# FAN_CONTROLER_LDO.net
KiCad netlist of a schematic drawn in EasyEDA
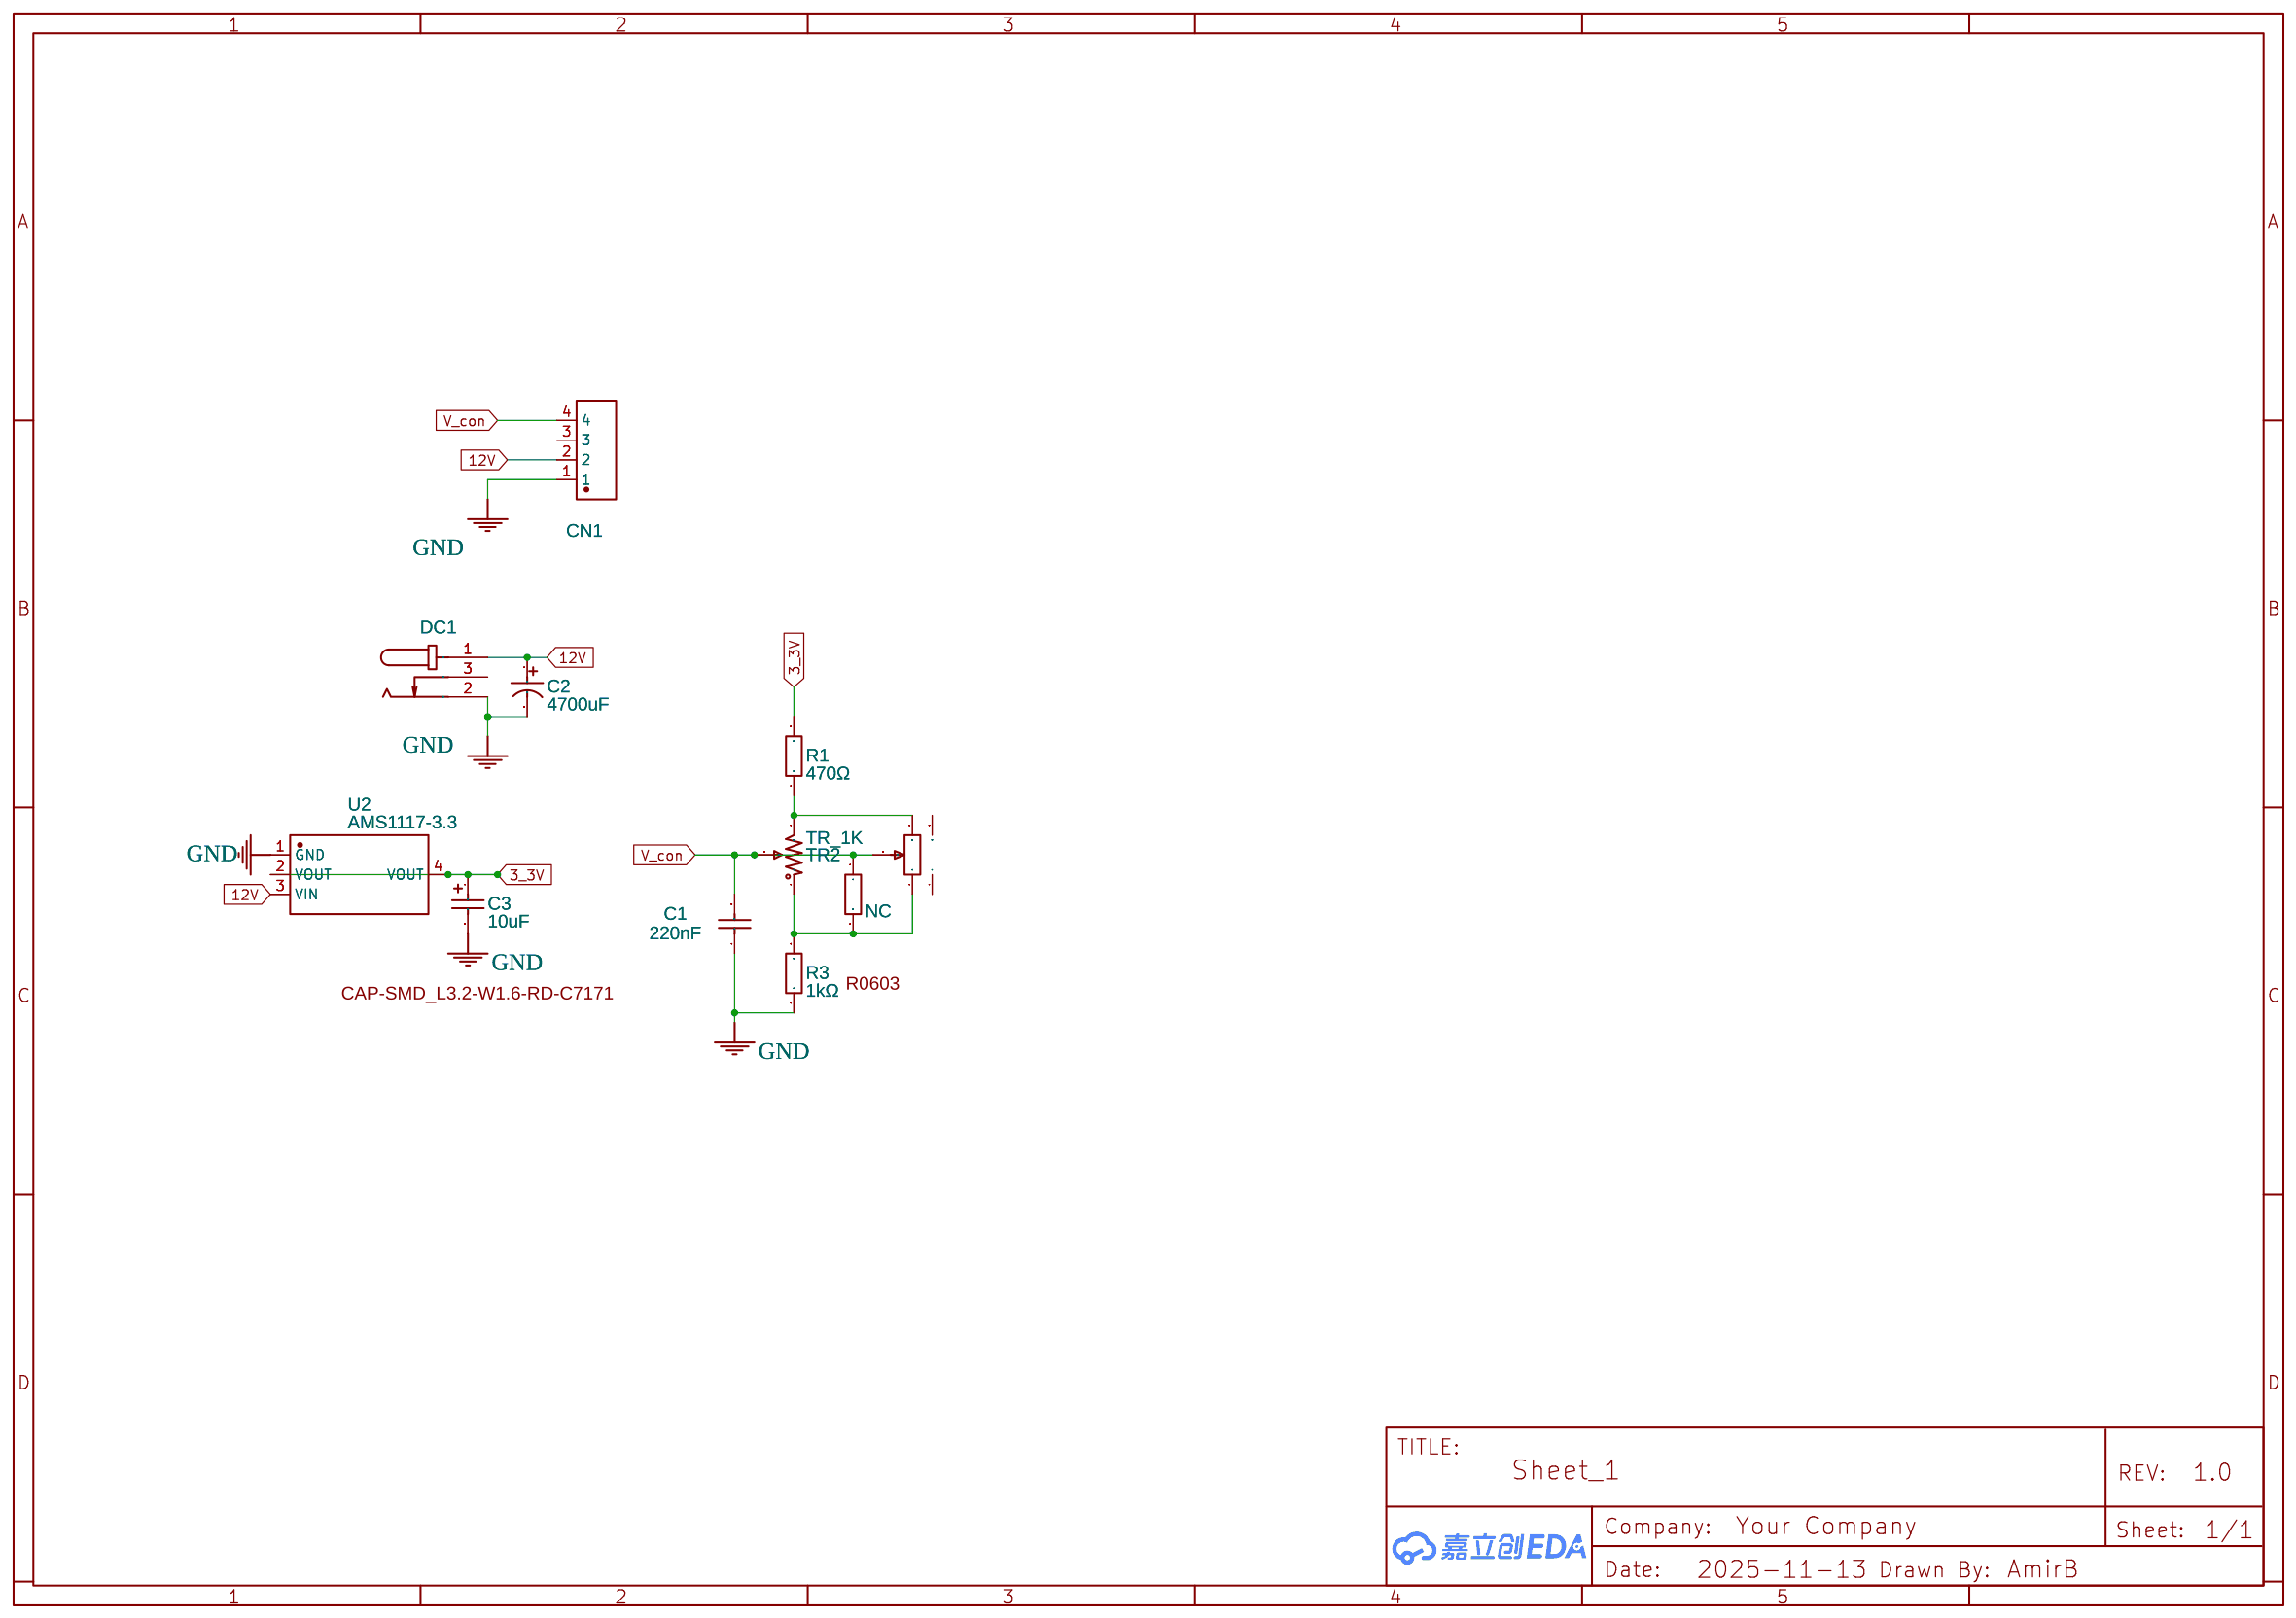
[diagram p0: schematic sheet]

(export (version "E")
  (design (tool "Eeschema 10.0.6"))
  (components
    (comp (ref "C1")
      (value "220nF")
      (fields
        (field (name "Manufacturer Part") "CL10B224KA8NNNC")
        (field (name "Manufacturer") "SAMSUNG(三星)")
      )
      (libsource (lib "") (part "CL10B224KA8NNNC"))
    )
    (comp (ref "C2")
      (value "4700uF")
      (fields
        (field (name "Manufacturer Part") "KM478M016J25RR0VH2FP0")
        (field (name "Manufacturer") "Chengx(承兴)")
      )
      (libsource (lib "") (part "4700uF16V"))
    )
    (comp (ref "C3")
      (value "10uF")
      (fields (field (name "Manufacturer Part") "TAJA106K016RNJ") (field (name "Manufacturer") "Kyocera AVX"))
      (libsource (lib "") (part "TAJA106K016RNJ"))
    )
    (comp (ref "CN1")
      (value "KF2510-4AGW-GW")
      (fields (field (name "Manufacturer") "CAX(创都)"))
      (libsource (lib "") (part "KF2510-4AGW-GW"))
    )
    (comp (ref "DC1")
      (value "DC")
      (fields
        (field (name "BOM_Manufacturer Part") "DC005-2.0MM")
        (field (name "BOM_Supplier Part") "C111567")
      )
      (libsource (lib "") (part "DC005-2.0MM"))
    )
    (comp (ref "NC")
      (value "NC")
      (fields
        (field (name "BOM_Manufacturer Part") "0603WAF1002T5E")
        (field (name "BOM_Supplier Part") "C25804")
      )
      (libsource (lib "") (part "0603WAF1002T5E"))
    )
    (comp (ref "POT_2")
      (value "POT_1K")
      (fields (field (name "BOM_Manufacturer Part") "长柄旋转电位器") (field (name "BOM_Supplier Part") "C2874842"))
      (libsource (lib "") (part "长柄旋转电位器"))
    )
    (comp (ref "R1")
      (value "470Ω")
      (fields
        (field (name "Manufacturer Part") "0603WAF4700T5E")
        (field (name "Manufacturer") "UNI-ROYAL(厚声)")
      )
      (libsource (lib "") (part "0603WAF4700T5E"))
    )
    (comp (ref "R3")
      (value "1kΩ")
      (fields
        (field (name "Manufacturer Part") "0603WAF1001T5E")
        (field (name "Manufacturer") "UNI-ROYAL(厚声)")
      )
      (libsource (lib "") (part "0603WAF1001T5E"))
    )
    (comp (ref "TR2")
      (value "TR_1K")
      (fields (field (name "Manufacturer Part") "3296W-1-202LF") (field (name "Manufacturer") "JIERR(捷而瑞)"))
      (libsource (lib "") (part "3296W-1-202LF_C49190458"))
    )
    (comp (ref "U2")
      (value "AMS1117-3.3")
      (fields (field (name "Manufacturer") "AMS"))
      (libsource (lib "") (part "AMS1117-3.3"))
    )
  )
  (nets
    (net (code "1") (name "3_3V") (class "Default")
      (node (ref "C3") (pin "1") (pinfunction "1_1") (pintype "input"))
      (node (ref "R1") (pin "2") (pinfunction "2_2") (pintype "input"))
      (node (ref "U2") (pin "2") (pinfunction "VOUT_2") (pintype "unspecified"))
      (node (ref "U2") (pin "4") (pinfunction "VOUT_4") (pintype "unspecified"))
    )
    (net (code "2") (name "12V") (class "Default")
      (node (ref "C2") (pin "1") (pinfunction "1_1") (pintype "input"))
      (node (ref "CN1") (pin "2") (pinfunction "2_2") (pintype "unspecified"))
      (node (ref "DC1") (pin "1") (pinfunction "1_1") (pintype "unspecified"))
      (node (ref "U2") (pin "3") (pinfunction "VIN_3") (pintype "unspecified"))
    )
    (net (code "3") (name "GND") (class "Default")
      (node (ref "C1") (pin "1") (pinfunction "1_1") (pintype "input"))
      (node (ref "C2") (pin "2") (pinfunction "2_2") (pintype "input"))
      (node (ref "C3") (pin "2") (pinfunction "2_2") (pintype "input"))
      (node (ref "CN1") (pin "1") (pinfunction "1_1") (pintype "unspecified"))
      (node (ref "DC1") (pin "2") (pinfunction "2_2") (pintype "unspecified"))
      (node (ref "R3") (pin "1") (pinfunction "1_1") (pintype "input"))
      (node (ref "U2") (pin "1") (pinfunction "GND_1") (pintype "unspecified"))
    )
    (net (code "4") (name "Net-(NC-Pad2)") (class "Default")
      (node (ref "NC") (pin "2") (pinfunction "2_2") (pintype "input"))
      (node (ref "POT_2") (pin "1") (pinfunction "1_1") (pintype "input"))
      (node (ref "R3") (pin "2") (pinfunction "2_2") (pintype "input"))
      (node (ref "TR2") (pin "1") (pinfunction "1_1") (pintype "unspecified"))
    )
    (net (code "5") (name "Net-(POT_2-Pad3)") (class "Default")
      (node (ref "POT_2") (pin "3") (pinfunction "3_3") (pintype "input"))
      (node (ref "R1") (pin "1") (pinfunction "1_1") (pintype "input"))
      (node (ref "TR2") (pin "3") (pinfunction "3_3") (pintype "unspecified"))
    )
    (net (code "6") (name "V_con") (class "Default")
      (node (ref "C1") (pin "2") (pinfunction "2_2") (pintype "input"))
      (node (ref "CN1") (pin "4") (pinfunction "4_4") (pintype "unspecified"))
      (node (ref "NC") (pin "1") (pinfunction "1_1") (pintype "input"))
      (node (ref "POT_2") (pin "2") (pinfunction "2_2") (pintype "input"))
      (node (ref "TR2") (pin "2") (pinfunction "2_2") (pintype "unspecified"))
    )
    (net (code "7") (name "unconnected-(CN1-Pad3)") (class "Default")
      (node (ref "CN1") (pin "3") (pinfunction "3_3") (pintype "unspecified"))
    )
    (net (code "8") (name "unconnected-(DC1-Pad3)") (class "Default")
      (node (ref "DC1") (pin "3") (pinfunction "3_3") (pintype "unspecified"))
    )
    (net (code "9") (name "unconnected-(POT_2-Pad4)") (class "Default")
      (node (ref "POT_2") (pin "4") (pinfunction "4_4") (pintype "input"))
    )
    (net (code "10") (name "unconnected-(POT_2-Pad5)") (class "Default")
      (node (ref "POT_2") (pin "5") (pinfunction "5_5") (pintype "input"))
    )
  )
)
